# LeBot.net
KiCad netlist of a schematic drawn in Altium Designer
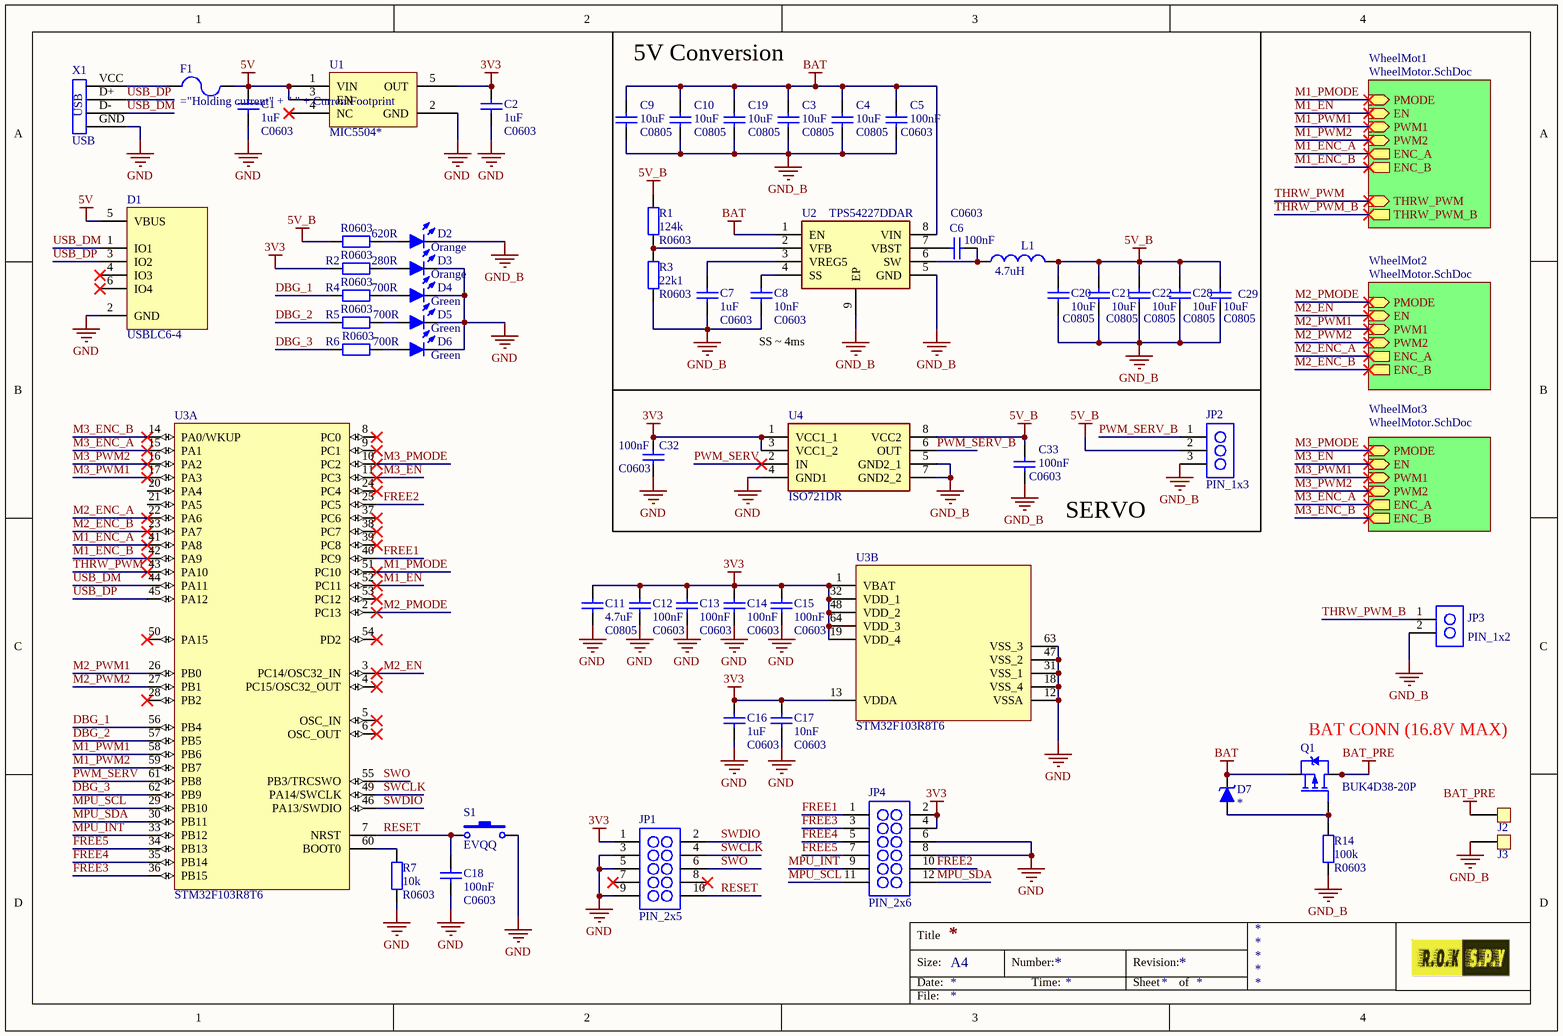
[diagram p0: LeBot.SchDoc]

(export (version "E")
  (design (tool "Eeschema 10.0.6"))
  (components
    (comp (ref "C1")
      (value "1uF*V")
      (footprint "C0603")
      (description "Ceramic capacitor")
      (fields (field (name "CAPACITANCE") "1uF"))
      (libsource (lib "SCH Passives") (part "Capacitor"))
    )
    (comp (ref "C2")
      (value "1uF*V")
      (footprint "C0603")
      (description "Ceramic capacitor")
      (fields (field (name "CAPACITANCE") "1uF"))
      (libsource (lib "SCH Passives") (part "Capacitor"))
    )
    (comp (ref "C3")
      (value "10uF*V")
      (footprint "C0805")
      (description "Ceramic capacitor")
      (fields (field (name "CAPACITANCE") "10uF"))
      (libsource (lib "SCH Passives") (part "Capacitor"))
    )
    (comp (ref "C4")
      (value "10uF*V")
      (footprint "C0805")
      (description "Ceramic capacitor")
      (fields (field (name "CAPACITANCE") "10uF"))
      (libsource (lib "SCH Passives") (part "Capacitor"))
    )
    (comp (ref "C5")
      (value "100nF*V")
      (footprint "C0603")
      (description "Ceramic capacitor")
      (fields (field (name "CAPACITANCE") "100nF"))
      (libsource (lib "SCH Passives") (part "Capacitor"))
    )
    (comp (ref "C6")
      (value "100nF*V")
      (footprint "C0603")
      (description "Ceramic capacitor")
      (fields (field (name "CAPACITANCE") "100nF"))
      (libsource (lib "SCH Passives") (part "Capacitor"))
    )
    (comp (ref "C7")
      (value "1uF*V")
      (footprint "C0603")
      (description "Ceramic capacitor")
      (fields (field (name "CAPACITANCE") "1uF"))
      (libsource (lib "SCH Passives") (part "Capacitor"))
    )
    (comp (ref "C8")
      (value "10nF*V")
      (footprint "C0603")
      (description "Ceramic capacitor")
      (fields (field (name "CAPACITANCE") "10nF"))
      (libsource (lib "SCH Passives") (part "Capacitor"))
    )
    (comp (ref "C9")
      (value "10uF*V")
      (footprint "C0805")
      (description "Ceramic capacitor")
      (fields (field (name "CAPACITANCE") "10uF"))
      (libsource (lib "SCH Passives") (part "Capacitor"))
    )
    (comp (ref "C10")
      (value "10uF*V")
      (footprint "C0805")
      (description "Ceramic capacitor")
      (fields (field (name "CAPACITANCE") "10uF"))
      (libsource (lib "SCH Passives") (part "Capacitor"))
    )
    (comp (ref "C11")
      (value "4.7uF*V")
      (footprint "C0805")
      (description "Ceramic capacitor")
      (fields (field (name "CAPACITANCE") "4.7uF"))
      (libsource (lib "SCH Passives") (part "Capacitor"))
    )
    (comp (ref "C12")
      (value "100nF*V")
      (footprint "C0603")
      (description "Ceramic capacitor")
      (fields (field (name "CAPACITANCE") "100nF"))
      (libsource (lib "SCH Passives") (part "Capacitor"))
    )
    (comp (ref "C13")
      (value "100nF*V")
      (footprint "C0603")
      (description "Ceramic capacitor")
      (fields (field (name "CAPACITANCE") "100nF"))
      (libsource (lib "SCH Passives") (part "Capacitor"))
    )
    (comp (ref "C14")
      (value "100nF*V")
      (footprint "C0603")
      (description "Ceramic capacitor")
      (fields (field (name "CAPACITANCE") "100nF"))
      (libsource (lib "SCH Passives") (part "Capacitor"))
    )
    (comp (ref "C15")
      (value "100nF*V")
      (footprint "C0603")
      (description "Ceramic capacitor")
      (fields (field (name "CAPACITANCE") "100nF"))
      (libsource (lib "SCH Passives") (part "Capacitor"))
    )
    (comp (ref "C16")
      (value "1uF*V")
      (footprint "C0603")
      (description "Ceramic capacitor")
      (fields (field (name "CAPACITANCE") "1uF"))
      (libsource (lib "SCH Passives") (part "Capacitor"))
    )
    (comp (ref "C17")
      (value "10nF*V")
      (footprint "C0603")
      (description "Ceramic capacitor")
      (fields (field (name "CAPACITANCE") "10nF"))
      (libsource (lib "SCH Passives") (part "Capacitor"))
    )
    (comp (ref "C18")
      (value "100nF*V")
      (footprint "C0603")
      (description "Ceramic capacitor")
      (fields (field (name "CAPACITANCE") "100nF"))
      (libsource (lib "SCH Passives") (part "Capacitor"))
    )
    (comp (ref "C19")
      (value "10uF*V")
      (footprint "C0805")
      (description "Ceramic capacitor")
      (fields (field (name "CAPACITANCE") "10uF"))
      (libsource (lib "SCH Passives") (part "Capacitor"))
    )
    (comp (ref "C20")
      (value "10uF*V")
      (footprint "C0805")
      (description "Ceramic capacitor")
      (fields (field (name "CAPACITANCE") "10uF"))
      (libsource (lib "SCH Passives") (part "Capacitor"))
    )
    (comp (ref "C21")
      (value "10uF*V")
      (footprint "C0805")
      (description "Ceramic capacitor")
      (fields (field (name "CAPACITANCE") "10uF"))
      (libsource (lib "SCH Passives") (part "Capacitor"))
    )
    (comp (ref "C22")
      (value "10uF*V")
      (footprint "C0805")
      (description "Ceramic capacitor")
      (fields (field (name "CAPACITANCE") "10uF"))
      (libsource (lib "SCH Passives") (part "Capacitor"))
    )
    (comp (ref "C28")
      (value "10uF*V")
      (footprint "C0805")
      (description "Ceramic capacitor")
      (fields (field (name "CAPACITANCE") "10uF"))
      (libsource (lib "SCH Passives") (part "Capacitor"))
    )
    (comp (ref "C29")
      (value "10uF*V")
      (footprint "C0805")
      (description "Ceramic capacitor")
      (fields (field (name "CAPACITANCE") "10uF"))
      (libsource (lib "SCH Passives") (part "Capacitor"))
    )
    (comp (ref "C32")
      (value "100nF*V")
      (footprint "C0603")
      (description "Ceramic capacitor")
      (fields (field (name "CAPACITANCE") "100nF"))
      (libsource (lib "SCH Passives") (part "Capacitor"))
    )
    (comp (ref "C33")
      (value "100nF*V")
      (footprint "C0603")
      (description "Ceramic capacitor")
      (fields (field (name "CAPACITANCE") "100nF"))
      (libsource (lib "SCH Passives") (part "Capacitor"))
    )
    (comp (ref "D1")
      (value "USBLC6-4")
      (footprint "SOT-236")
      (description "USB ESD Protection")
      (fields (field (name "MANUFACTURER") "ST Microelectronics"))
      (libsource (lib "SCH Diodes") (part "USBLC6-4"))
    )
    (comp (ref "D2")
      (value "~")
      (footprint "Diodes:LED_0805")
      (description "Light Emitting Diode")
      (fields (field (name "PART NUMBER") "MC011368") (field (name "COLOUR") "Orange"))
      (libsource (lib "Diodes") (part "LED"))
    )
    (comp (ref "D3")
      (value "~")
      (footprint "Diodes:LED_0805")
      (description "Light Emitting Diode")
      (fields (field (name "PART NUMBER") "MC011368") (field (name "COLOUR") "Orange"))
      (libsource (lib "Diodes") (part "LED"))
    )
    (comp (ref "D4")
      (value "~")
      (footprint "Diodes:LED_0805")
      (description "Light Emitting Diode")
      (fields (field (name "PART NUMBER") "KP-2012LSGC") (field (name "COLOUR") "Green"))
      (libsource (lib "Diodes") (part "LED"))
    )
    (comp (ref "D5")
      (value "~")
      (footprint "Diodes:LED_0805")
      (description "Light Emitting Diode")
      (fields (field (name "PART NUMBER") "KP-2012LSGC") (field (name "COLOUR") "Green"))
      (libsource (lib "Diodes") (part "LED"))
    )
    (comp (ref "D6")
      (value "~")
      (footprint "Diodes:LED_0805")
      (description "Light Emitting Diode")
      (fields (field (name "PART NUMBER") "KP-2012LSGC") (field (name "COLOUR") "Green"))
      (libsource (lib "Diodes") (part "LED"))
    )
    (comp (ref "D7")
      (value "*")
      (footprint "Diodes:SOT23-Zener")
      (libsource (lib "Diodes") (part "Zener Diode"))
    )
    (comp (ref "F1")
      (value "*A")
      (footprint "F1210")
      (description "Fuse")
      (fields (field (name "NOTE") "*A"))
      (libsource (lib "SCH Passives") (part "Fuse"))
    )
    (comp (ref "J2")
      (value "Connection_pad")
      (footprint "Connectors:Wire_Pad")
      (libsource (lib "Connectors") (part "Connection_pad"))
    )
    (comp (ref "J3")
      (value "Connection_pad")
      (footprint "Connectors:Wire_Pad")
      (libsource (lib "Connectors") (part "Connection_pad"))
    )
    (comp (ref "JP1")
      (value "PIN_2x5")
      (footprint "1.27_2X5H")
      (fields (field (name "DRAWN BY") "Erik Ilbis"))
      (libsource (lib "SCH Pinhead") (part "PIN_2x5"))
    )
    (comp (ref "JP2")
      (value "PIN_1x3")
      (footprint "1.27_1X3H")
      (fields (field (name "DRAWN BY") "Erik Ilbis"))
      (libsource (lib "SCH Pinhead") (part "PIN_1x3"))
    )
    (comp (ref "JP3")
      (value "PIN_1x2")
      (footprint "1.27_1X2H")
      (fields (field (name "DRAWN BY") "Erik Ilbis"))
      (libsource (lib "SCH Pinhead") (part "PIN_1x2"))
    )
    (comp (ref "JP4")
      (value "PIN_2x6")
      (footprint "1.27_2X6H")
      (fields (field (name "DRAWN BY") "Erik Ilbis"))
      (libsource (lib "SCH Pinhead") (part "PIN_2x6"))
    )
    (comp (ref "L1")
      (value "Inductor")
      (footprint "L73")
      (fields (field (name "INDUCTANCE") "4.7uH"))
      (libsource (lib "SCH Passives") (part "Inductor"))
    )
    (comp (ref "Q1")
      (value "BUK4D38-20P")
      (footprint "PMPB12EPX")
      (description "P-Channel MOSFET")
      (libsource (lib "Transistors") (part "P-Channel MOSFET"))
    )
    (comp (ref "R1")
      (value "124k")
      (footprint "R0603")
      (description "Resistor")
      (fields (field (name "RESISTANCE") "124k"))
      (libsource (lib "SCH Passives") (part "Resistor"))
    )
    (comp (ref "R2")
      (value "280R")
      (footprint "R0603")
      (description "Resistor")
      (fields (field (name "RESISTANCE") "280R"))
      (libsource (lib "") (part "Resistor_1"))
    )
    (comp (ref "R3")
      (value "22k1")
      (footprint "R0603")
      (description "Resistor")
      (fields (field (name "RESISTANCE") "22k1"))
      (libsource (lib "SCH Passives") (part "Resistor"))
    )
    (comp (ref "R4")
      (value "700R")
      (footprint "R0603")
      (description "Resistor")
      (fields (field (name "RESISTANCE") "700R"))
      (libsource (lib "") (part "Resistor_1"))
    )
    (comp (ref "R5")
      (value "700R")
      (footprint "R0603")
      (description "Resistor")
      (fields (field (name "RESISTANCE") "700R"))
      (libsource (lib "") (part "Resistor_1"))
    )
    (comp (ref "R6")
      (value "700R")
      (footprint "R0603")
      (description "Resistor")
      (fields (field (name "RESISTANCE") "700R"))
      (libsource (lib "") (part "Resistor_1"))
    )
    (comp (ref "R7")
      (value "10k")
      (footprint "R0603")
      (description "Resistor")
      (fields (field (name "RESISTANCE") "10k"))
      (libsource (lib "SCH Passives") (part "Resistor"))
    )
    (comp (ref "R8")
      (value "620R")
      (footprint "R0603")
      (description "Resistor")
      (fields (field (name "RESISTANCE") "620R"))
      (libsource (lib "") (part "Resistor_1"))
    )
    (comp (ref "R14")
      (value "100k")
      (footprint "R0603")
      (description "Resistor")
      (fields (field (name "RESISTANCE") "100k"))
      (libsource (lib "") (part "Resistor_2"))
    )
    (comp (ref "S1")
      (value "EVQQ")
      (footprint "EVQQ")
      (description "Switch")
      (fields
        (field (name "MANUFACTURER") "Panasonic")
        (field (name "PART NUMBER") "EVQQ")
        (field (name "DRAWN BY") "Erik Ilbis")
      )
      (libsource (lib "SCH Switch") (part "EVQQ"))
    )
    (comp (ref "U1")
      (value "MIC5504*")
      (footprint "SOT-235")
      (description "Low-dropout voltage regulator")
      (fields
        (field (name "MANUFACTURER") "Microchip/Micrel")
        (field (name "PART NUMBER") "MIC5504")
        (field (name "DRAWN BY") "Roberts Oskars Komarovskis")
      )
      (libsource (lib "SCH Voltage regulators") (part "MIC5504"))
    )
    (comp (ref "U2")
      (value "TPS54227DDAR")
      (footprint "Voltage Regulators:SOIC127P600X175-8N")
      (description "4.5-V to 18-V Input, 2-A SynchronousStep-DownConverter")
      (libsource (lib "Voltage Regulators") (part "TPS54227DDAR"))
    )
    (comp (ref "U3")
      (value "STM32F103R8T6")
      (footprint "MCU:QFP50P1200X1200X160-64N")
      (fields (field (name "DRAWN BY") "Roberts Oskars Komarovskis"))
      (libsource (lib "MCU") (part "STM32F103R8T6"))
    )
    (comp (ref "U4")
      (value "ISO721DR")
      (footprint "Voltage Regulators:SOIC127P600X175-8N")
      (description "SO72xSingleChannelHigh-SpeedDigitalIsolators")
      (libsource (lib "Misc") (part "ISO721DR"))
    )
    (comp (ref "X1")
      (value "USB")
      (footprint "USB MicroB Type 2.0")
      (libsource (lib "SCH Connectors") (part "USB"))
    )
  )
  (nets
    (net (code "1") (name "/DBG_1") (class "Default")
      (node (ref "R4") (pin "2") (pinfunction "2_2") (pintype "passive"))
      (node (ref "U3") (pin "56") (pinfunction "PB4_56") (pintype "bidirectional"))
    )
    (net (code "2") (name "/DBG_2") (class "Default")
      (node (ref "R5") (pin "2") (pinfunction "2_2") (pintype "passive"))
      (node (ref "U3") (pin "57") (pinfunction "PB5_57") (pintype "bidirectional"))
    )
    (net (code "3") (name "/DBG_3") (class "Default")
      (node (ref "R6") (pin "2") (pinfunction "2_2") (pintype "passive"))
      (node (ref "U3") (pin "62") (pinfunction "PB9_62") (pintype "bidirectional"))
    )
    (net (code "4") (name "/FREE1") (class "Default")
      (node (ref "JP4") (pin "1") (pinfunction "1_1") (pintype "passive"))
      (node (ref "U3") (pin "40") (pinfunction "PC9_40") (pintype "bidirectional"))
    )
    (net (code "5") (name "/FREE2") (class "Default")
      (node (ref "JP4") (pin "10") (pinfunction "10_10") (pintype "passive"))
      (node (ref "U3") (pin "25") (pinfunction "PC5_25") (pintype "bidirectional"))
    )
    (net (code "6") (name "/FREE3") (class "Default")
      (node (ref "JP4") (pin "3") (pinfunction "3_3") (pintype "passive"))
      (node (ref "U3") (pin "36") (pinfunction "PB15_36") (pintype "bidirectional"))
    )
    (net (code "7") (name "/FREE4") (class "Default")
      (node (ref "JP4") (pin "5") (pinfunction "5_5") (pintype "passive"))
      (node (ref "U3") (pin "35") (pinfunction "PB14_35") (pintype "bidirectional"))
    )
    (net (code "8") (name "/FREE5") (class "Default")
      (node (ref "JP4") (pin "7") (pinfunction "7_7") (pintype "passive"))
      (node (ref "U3") (pin "34") (pinfunction "PB13_34") (pintype "bidirectional"))
    )
    (net (code "9") (name "/M1_EN") (class "Default")
      (node (ref "U3") (pin "52") (pinfunction "PC11_52") (pintype "bidirectional+no_connect"))
    )
    (net (code "10") (name "/M1_ENC_A") (class "Default")
      (node (ref "U3") (pin "41") (pinfunction "PA8_41") (pintype "bidirectional+no_connect"))
    )
    (net (code "11") (name "/M1_ENC_B") (class "Default")
      (node (ref "U3") (pin "42") (pinfunction "PA9_42") (pintype "bidirectional+no_connect"))
    )
    (net (code "12") (name "/M1_PMODE") (class "Default")
      (node (ref "U3") (pin "51") (pinfunction "PC10_51") (pintype "bidirectional+no_connect"))
    )
    (net (code "13") (name "/M1_PWM1") (class "Default")
      (node (ref "U3") (pin "58") (pinfunction "PB6_58") (pintype "bidirectional"))
    )
    (net (code "14") (name "/M1_PWM2") (class "Default")
      (node (ref "U3") (pin "59") (pinfunction "PB7_59") (pintype "bidirectional"))
    )
    (net (code "15") (name "/M2_EN") (class "Default")
      (node (ref "U3") (pin "3") (pinfunction "PC14/OSC32_IN_3") (pintype "bidirectional+no_connect"))
    )
    (net (code "16") (name "/M2_ENC_A") (class "Default")
      (node (ref "U3") (pin "22") (pinfunction "PA6_22") (pintype "bidirectional+no_connect"))
    )
    (net (code "17") (name "/M2_ENC_B") (class "Default")
      (node (ref "U3") (pin "23") (pinfunction "PA7_23") (pintype "bidirectional+no_connect"))
    )
    (net (code "18") (name "/M2_PMODE") (class "Default")
      (node (ref "U3") (pin "2") (pinfunction "PC13_2") (pintype "bidirectional+no_connect"))
    )
    (net (code "19") (name "/M2_PWM1") (class "Default")
      (node (ref "U3") (pin "26") (pinfunction "PB0_26") (pintype "bidirectional"))
    )
    (net (code "20") (name "/M2_PWM2") (class "Default")
      (node (ref "U3") (pin "27") (pinfunction "PB1_27") (pintype "bidirectional"))
    )
    (net (code "21") (name "/M3_EN") (class "Default")
      (node (ref "U3") (pin "11") (pinfunction "PC3_11") (pintype "bidirectional+no_connect"))
    )
    (net (code "22") (name "/M3_ENC_A") (class "Default")
      (node (ref "U3") (pin "15") (pinfunction "PA1_15") (pintype "bidirectional+no_connect"))
    )
    (net (code "23") (name "/M3_ENC_B") (class "Default")
      (node (ref "U3") (pin "14") (pinfunction "PA0/WKUP_14") (pintype "bidirectional+no_connect"))
    )
    (net (code "24") (name "/M3_PMODE") (class "Default")
      (node (ref "U3") (pin "10") (pinfunction "PC2_10") (pintype "bidirectional+no_connect"))
    )
    (net (code "25") (name "/M3_PWM1") (class "Default")
      (node (ref "U3") (pin "17") (pinfunction "PA3_17") (pintype "bidirectional+no_connect"))
    )
    (net (code "26") (name "/M3_PWM2") (class "Default")
      (node (ref "U3") (pin "16") (pinfunction "PA2_16") (pintype "bidirectional+no_connect"))
    )
    (net (code "27") (name "/MPU_INT") (class "Default")
      (node (ref "JP4") (pin "9") (pinfunction "9_9") (pintype "passive"))
      (node (ref "U3") (pin "33") (pinfunction "PB12_33") (pintype "bidirectional"))
    )
    (net (code "28") (name "/MPU_SCL") (class "Default")
      (node (ref "JP4") (pin "11") (pinfunction "11_11") (pintype "passive"))
      (node (ref "U3") (pin "29") (pinfunction "PB10_29") (pintype "bidirectional"))
    )
    (net (code "29") (name "/MPU_SDA") (class "Default")
      (node (ref "JP4") (pin "12") (pinfunction "12_12") (pintype "passive"))
      (node (ref "U3") (pin "30") (pinfunction "PB11_30") (pintype "bidirectional"))
    )
    (net (code "30") (name "/PWM_SERV") (class "Default")
      (node (ref "U3") (pin "61") (pinfunction "PB8_61") (pintype "bidirectional"))
      (node (ref "U4") (pin "2") (pinfunction "IN_2") (pintype "passive"))
    )
    (net (code "31") (name "/PWM_SERV_B") (class "Default")
      (node (ref "JP2") (pin "1") (pinfunction "1_1") (pintype "passive"))
      (node (ref "U4") (pin "6") (pinfunction "OUT_6") (pintype "passive"))
    )
    (net (code "32") (name "/RESET") (class "Default")
      (node (ref "C18") (pin "2") (pinfunction "2_2") (pintype "passive"))
      (node (ref "JP1") (pin "10") (pinfunction "10_10") (pintype "passive"))
      (node (ref "S1") (pin "1") (pinfunction "1_1") (pintype "passive"))
      (node (ref "U3") (pin "7") (pinfunction "NRST_7") (pintype "passive"))
    )
    (net (code "33") (name "/SWCLK") (class "Default")
      (node (ref "JP1") (pin "4") (pinfunction "4_4") (pintype "passive"))
      (node (ref "U3") (pin "49") (pinfunction "PA14/SWCLK_49") (pintype "bidirectional"))
    )
    (net (code "34") (name "/SWDIO") (class "Default")
      (node (ref "JP1") (pin "2") (pinfunction "2_2") (pintype "passive"))
      (node (ref "U3") (pin "46") (pinfunction "PA13/SWDIO_46") (pintype "bidirectional"))
    )
    (net (code "35") (name "/SWO") (class "Default")
      (node (ref "JP1") (pin "6") (pinfunction "6_6") (pintype "passive"))
      (node (ref "U3") (pin "55") (pinfunction "PB3/TRCSWO_55") (pintype "bidirectional"))
    )
    (net (code "36") (name "/THRW_PWM") (class "Default")
      (node (ref "U3") (pin "43") (pinfunction "PA10_43") (pintype "bidirectional+no_connect"))
    )
    (net (code "37") (name "/THRW_PWM_B") (class "Default")
      (node (ref "JP3") (pin "1") (pinfunction "1_1") (pintype "passive"))
    )
    (net (code "38") (name "/USB_DM") (class "Default")
      (node (ref "D1") (pin "1") (pinfunction "IO1_1") (pintype "passive"))
      (node (ref "U3") (pin "44") (pinfunction "PA11_44") (pintype "bidirectional"))
      (node (ref "X1") (pin "D-") (pintype "passive"))
    )
    (net (code "39") (name "/USB_DP") (class "Default")
      (node (ref "D1") (pin "3") (pinfunction "IO2_3") (pintype "passive"))
      (node (ref "U3") (pin "45") (pinfunction "PA12_45") (pintype "bidirectional"))
      (node (ref "X1") (pin "D+") (pintype "passive"))
    )
    (net (code "40") (name "3V3") (class "Default")
      (node (ref "C11") (pin "2") (pinfunction "2_2") (pintype "passive"))
      (node (ref "C12") (pin "2") (pinfunction "2_2") (pintype "passive"))
      (node (ref "C13") (pin "2") (pinfunction "2_2") (pintype "passive"))
      (node (ref "C14") (pin "2") (pinfunction "2_2") (pintype "passive"))
      (node (ref "C15") (pin "2") (pinfunction "2_2") (pintype "passive"))
      (node (ref "C16") (pin "2") (pinfunction "2_2") (pintype "passive"))
      (node (ref "C17") (pin "2") (pinfunction "2_2") (pintype "passive"))
      (node (ref "C2") (pin "2") (pinfunction "2_2") (pintype "passive"))
      (node (ref "C32") (pin "2") (pinfunction "2_2") (pintype "passive"))
      (node (ref "JP1") (pin "1") (pinfunction "1_1") (pintype "passive"))
      (node (ref "JP4") (pin "2") (pinfunction "2_2") (pintype "passive"))
      (node (ref "JP4") (pin "4") (pinfunction "4_4") (pintype "passive"))
      (node (ref "R2") (pin "2") (pinfunction "2_2") (pintype "passive"))
      (node (ref "U1") (pin "5") (pinfunction "OUT_5") (pintype "passive"))
      (node (ref "U3") (pin "1") (pinfunction "VBAT_1") (pintype "passive"))
      (node (ref "U3") (pin "13") (pinfunction "VDDA_13") (pintype "passive"))
      (node (ref "U3") (pin "19") (pinfunction "VDD_4_19") (pintype "passive"))
      (node (ref "U3") (pin "32") (pinfunction "VDD_1_32") (pintype "passive"))
      (node (ref "U3") (pin "48") (pinfunction "VDD_2_48") (pintype "passive"))
      (node (ref "U3") (pin "64") (pinfunction "VDD_3_64") (pintype "passive"))
      (node (ref "U4") (pin "1") (pinfunction "VCC1_1_1") (pintype "passive"))
      (node (ref "U4") (pin "3") (pinfunction "VCC1_2_3") (pintype "passive"))
    )
    (net (code "41") (name "5V") (class "Default")
      (node (ref "C1") (pin "2") (pinfunction "2_2") (pintype "passive"))
      (node (ref "D1") (pin "5") (pinfunction "VBUS_5") (pintype "passive"))
      (node (ref "F1") (pin "2") (pinfunction "2_2") (pintype "passive"))
      (node (ref "U1") (pin "1") (pinfunction "VIN_1") (pintype "passive"))
      (node (ref "U1") (pin "3") (pinfunction "EN_3") (pintype "passive"))
    )
    (net (code "42") (name "5V_B") (class "Default")
      (node (ref "C20") (pin "2") (pinfunction "2_2") (pintype "passive"))
      (node (ref "C21") (pin "2") (pinfunction "2_2") (pintype "passive"))
      (node (ref "C22") (pin "2") (pinfunction "2_2") (pintype "passive"))
      (node (ref "C28") (pin "2") (pinfunction "2_2") (pintype "passive"))
      (node (ref "C29") (pin "2") (pinfunction "2_2") (pintype "passive"))
      (node (ref "C33") (pin "2") (pinfunction "2_2") (pintype "passive"))
      (node (ref "JP2") (pin "2") (pinfunction "2_2") (pintype "passive"))
      (node (ref "L1") (pin "2") (pinfunction "2_2") (pintype "passive"))
      (node (ref "R1") (pin "2") (pinfunction "2_2") (pintype "passive"))
      (node (ref "R8") (pin "2") (pinfunction "2_2") (pintype "passive"))
      (node (ref "U4") (pin "8") (pinfunction "VCC2_8") (pintype "passive"))
    )
    (net (code "43") (name "BAT") (class "Default")
      (node (ref "C10") (pin "2") (pinfunction "2_2") (pintype "passive"))
      (node (ref "C19") (pin "2") (pinfunction "2_2") (pintype "passive"))
      (node (ref "C3") (pin "2") (pinfunction "2_2") (pintype "passive"))
      (node (ref "C4") (pin "2") (pinfunction "2_2") (pintype "passive"))
      (node (ref "C5") (pin "2") (pinfunction "2_2") (pintype "passive"))
      (node (ref "C9") (pin "2") (pinfunction "2_2") (pintype "passive"))
      (node (ref "D7") (pin "2") (pinfunction "K_2") (pintype "passive"))
      (node (ref "Q1") (pin "1") (pinfunction "S_1") (pintype "passive"))
      (node (ref "U2") (pin "1") (pinfunction "EN_1") (pintype "passive"))
      (node (ref "U2") (pin "8") (pinfunction "VIN_8") (pintype "passive"))
    )
    (net (code "44") (name "BAT_PRE") (class "Default")
      (node (ref "J2") (pin "1") (pinfunction "*_1") (pintype "passive"))
      (node (ref "Q1") (pin "3") (pinfunction "D_3") (pintype "passive"))
      (node (ref "Q1") (pin "D0") (pinfunction "D_D0") (pintype "passive"))
      (node (ref "Q1") (pin "D1") (pinfunction "D_D1") (pintype "passive"))
      (node (ref "Q1") (pin "D2") (pinfunction "D_D2") (pintype "passive"))
    )
    (net (code "45") (name "GND") (class "Default")
      (node (ref "C1") (pin "1") (pinfunction "1_1") (pintype "passive"))
      (node (ref "C11") (pin "1") (pinfunction "1_1") (pintype "passive"))
      (node (ref "C12") (pin "1") (pinfunction "1_1") (pintype "passive"))
      (node (ref "C13") (pin "1") (pinfunction "1_1") (pintype "passive"))
      (node (ref "C14") (pin "1") (pinfunction "1_1") (pintype "passive"))
      (node (ref "C15") (pin "1") (pinfunction "1_1") (pintype "passive"))
      (node (ref "C16") (pin "1") (pinfunction "1_1") (pintype "passive"))
      (node (ref "C17") (pin "1") (pinfunction "1_1") (pintype "passive"))
      (node (ref "C18") (pin "1") (pinfunction "1_1") (pintype "passive"))
      (node (ref "C2") (pin "1") (pinfunction "1_1") (pintype "passive"))
      (node (ref "C32") (pin "1") (pinfunction "1_1") (pintype "passive"))
      (node (ref "D1") (pin "2") (pinfunction "GND_2") (pintype "passive"))
      (node (ref "D3") (pin "2") (pinfunction "K_2") (pintype "passive"))
      (node (ref "D4") (pin "2") (pinfunction "K_2") (pintype "passive"))
      (node (ref "D5") (pin "2") (pinfunction "K_2") (pintype "passive"))
      (node (ref "D6") (pin "2") (pinfunction "K_2") (pintype "passive"))
      (node (ref "JP1") (pin "3") (pinfunction "3_3") (pintype "passive"))
      (node (ref "JP1") (pin "5") (pinfunction "5_5") (pintype "passive"))
      (node (ref "JP1") (pin "9") (pinfunction "9_9") (pintype "passive"))
      (node (ref "JP4") (pin "6") (pinfunction "6_6") (pintype "passive"))
      (node (ref "JP4") (pin "8") (pinfunction "8_8") (pintype "passive"))
      (node (ref "R7") (pin "1") (pinfunction "1_1") (pintype "passive"))
      (node (ref "S1") (pin "2") (pinfunction "2_2") (pintype "passive"))
      (node (ref "U1") (pin "2") (pinfunction "GND_2") (pintype "passive"))
      (node (ref "U3") (pin "12") (pinfunction "VSSA_12") (pintype "passive"))
      (node (ref "U3") (pin "18") (pinfunction "VSS_4_18") (pintype "passive"))
      (node (ref "U3") (pin "31") (pinfunction "VSS_1_31") (pintype "passive"))
      (node (ref "U3") (pin "47") (pinfunction "VSS_2_47") (pintype "passive"))
      (node (ref "U3") (pin "63") (pinfunction "VSS_3_63") (pintype "passive"))
      (node (ref "U4") (pin "4") (pinfunction "GND1_4") (pintype "passive"))
      (node (ref "X1") (pin "GND") (pintype "passive"))
    )
    (net (code "46") (name "GND_B") (class "Default")
      (node (ref "C10") (pin "1") (pinfunction "1_1") (pintype "passive"))
      (node (ref "C19") (pin "1") (pinfunction "1_1") (pintype "passive"))
      (node (ref "C20") (pin "1") (pinfunction "1_1") (pintype "passive"))
      (node (ref "C21") (pin "1") (pinfunction "1_1") (pintype "passive"))
      (node (ref "C22") (pin "1") (pinfunction "1_1") (pintype "passive"))
      (node (ref "C28") (pin "1") (pinfunction "1_1") (pintype "passive"))
      (node (ref "C29") (pin "1") (pinfunction "1_1") (pintype "passive"))
      (node (ref "C3") (pin "1") (pinfunction "1_1") (pintype "passive"))
      (node (ref "C33") (pin "1") (pinfunction "1_1") (pintype "passive"))
      (node (ref "C4") (pin "1") (pinfunction "1_1") (pintype "passive"))
      (node (ref "C5") (pin "1") (pinfunction "1_1") (pintype "passive"))
      (node (ref "C7") (pin "1") (pinfunction "1_1") (pintype "passive"))
      (node (ref "C8") (pin "1") (pinfunction "1_1") (pintype "passive"))
      (node (ref "C9") (pin "1") (pinfunction "1_1") (pintype "passive"))
      (node (ref "D2") (pin "2") (pinfunction "K_2") (pintype "passive"))
      (node (ref "J3") (pin "1") (pinfunction "*_1") (pintype "passive"))
      (node (ref "JP2") (pin "3") (pinfunction "3_3") (pintype "passive"))
      (node (ref "JP3") (pin "2") (pinfunction "2_2") (pintype "passive"))
      (node (ref "R14") (pin "2") (pinfunction "2_2") (pintype "passive"))
      (node (ref "R3") (pin "1") (pinfunction "1_1") (pintype "passive"))
      (node (ref "U2") (pin "5") (pinfunction "GND_5") (pintype "passive"))
      (node (ref "U2") (pin "9") (pinfunction "EP_9") (pintype "passive"))
      (node (ref "U4") (pin "5") (pinfunction "GND2_1_5") (pintype "passive"))
      (node (ref "U4") (pin "7") (pinfunction "GND2_2_7") (pintype "passive"))
    )
    (net (code "47") (name "Net-(D2-A)") (class "Default")
      (node (ref "D2") (pin "1") (pinfunction "A_1") (pintype "passive"))
      (node (ref "R8") (pin "1") (pinfunction "1_1") (pintype "passive"))
    )
    (net (code "48") (name "Net-(D3-A)") (class "Default")
      (node (ref "D3") (pin "1") (pinfunction "A_1") (pintype "passive"))
      (node (ref "R2") (pin "1") (pinfunction "1_1") (pintype "passive"))
    )
    (net (code "49") (name "Net-(D4-A)") (class "Default")
      (node (ref "D4") (pin "1") (pinfunction "A_1") (pintype "passive"))
      (node (ref "R4") (pin "1") (pinfunction "1_1") (pintype "passive"))
    )
    (net (code "50") (name "Net-(D5-A)") (class "Default")
      (node (ref "D5") (pin "1") (pinfunction "A_1") (pintype "passive"))
      (node (ref "R5") (pin "1") (pinfunction "1_1") (pintype "passive"))
    )
    (net (code "51") (name "Net-(D6-A)") (class "Default")
      (node (ref "D6") (pin "1") (pinfunction "A_1") (pintype "passive"))
      (node (ref "R6") (pin "1") (pinfunction "1_1") (pintype "passive"))
    )
    (net (code "52") (name "Net-(D7-A)") (class "Default")
      (node (ref "D7") (pin "1") (pinfunction "A_1") (pintype "passive"))
      (node (ref "Q1") (pin "2") (pinfunction "G_2") (pintype "passive"))
      (node (ref "R14") (pin "1") (pinfunction "1_1") (pintype "passive"))
    )
    (net (code "53") (name "Net-(F1-Pad1)") (class "Default")
      (node (ref "F1") (pin "1") (pinfunction "1_1") (pintype "passive"))
      (node (ref "X1") (pin "VCC") (pintype "passive"))
    )
    (net (code "54") (name "Net-(U2-SS)") (class "Default")
      (node (ref "C8") (pin "2") (pinfunction "2_2") (pintype "passive"))
      (node (ref "U2") (pin "4") (pinfunction "SS_4") (pintype "passive"))
    )
    (net (code "55") (name "Net-(U2-SW)") (class "Default")
      (node (ref "C6") (pin "1") (pinfunction "1_1") (pintype "passive"))
      (node (ref "L1") (pin "1") (pinfunction "1_1") (pintype "passive"))
      (node (ref "U2") (pin "6") (pinfunction "SW_6") (pintype "passive"))
    )
    (net (code "56") (name "Net-(U2-VBST)") (class "Default")
      (node (ref "C6") (pin "2") (pinfunction "2_2") (pintype "passive"))
      (node (ref "U2") (pin "7") (pinfunction "VBST_7") (pintype "passive"))
    )
    (net (code "57") (name "Net-(U2-VFB)") (class "Default")
      (node (ref "R1") (pin "1") (pinfunction "1_1") (pintype "passive"))
      (node (ref "R3") (pin "2") (pinfunction "2_2") (pintype "passive"))
      (node (ref "U2") (pin "2") (pinfunction "VFB_2") (pintype "passive"))
    )
    (net (code "58") (name "Net-(U2-VREG5)") (class "Default")
      (node (ref "C7") (pin "2") (pinfunction "2_2") (pintype "passive"))
      (node (ref "U2") (pin "3") (pinfunction "VREG5_3") (pintype "passive"))
    )
    (net (code "59") (name "Net-(U3A-BOOT0)") (class "Default")
      (node (ref "R7") (pin "2") (pinfunction "2_2") (pintype "passive"))
      (node (ref "U3") (pin "60") (pinfunction "BOOT0_60") (pintype "passive"))
    )
    (net (code "60") (name "unconnected-(D1-IO3-Pad4)") (class "Default")
      (node (ref "D1") (pin "4") (pinfunction "IO3_4") (pintype "passive+no_connect"))
    )
    (net (code "61") (name "unconnected-(D1-IO4-Pad6)") (class "Default")
      (node (ref "D1") (pin "6") (pinfunction "IO4_6") (pintype "passive+no_connect"))
    )
    (net (code "62") (name "unconnected-(JP1-Pad7)") (class "Default")
      (node (ref "JP1") (pin "7") (pinfunction "7_7") (pintype "passive+no_connect"))
    )
    (net (code "63") (name "unconnected-(JP1-Pad8)") (class "Default")
      (node (ref "JP1") (pin "8") (pinfunction "8_8") (pintype "passive+no_connect"))
    )
    (net (code "64") (name "unconnected-(U1-NC-Pad4)") (class "Default")
      (node (ref "U1") (pin "4") (pinfunction "NC_4") (pintype "passive+no_connect"))
    )
    (net (code "65") (name "unconnected-(U3A-OSC_IN-Pad5)") (class "Default")
      (node (ref "U3") (pin "5") (pinfunction "OSC_IN_5") (pintype "bidirectional+no_connect"))
    )
    (net (code "66") (name "unconnected-(U3A-OSC_OUT-Pad6)") (class "Default")
      (node (ref "U3") (pin "6") (pinfunction "OSC_OUT_6") (pintype "bidirectional+no_connect"))
    )
    (net (code "67") (name "unconnected-(U3A-PA4-Pad20)") (class "Default")
      (node (ref "U3") (pin "20") (pinfunction "PA4_20") (pintype "bidirectional"))
    )
    (net (code "68") (name "unconnected-(U3A-PA5-Pad21)") (class "Default")
      (node (ref "U3") (pin "21") (pinfunction "PA5_21") (pintype "bidirectional"))
    )
    (net (code "69") (name "unconnected-(U3A-PA15-Pad50)") (class "Default")
      (node (ref "U3") (pin "50") (pinfunction "PA15_50") (pintype "bidirectional+no_connect"))
    )
    (net (code "70") (name "unconnected-(U3A-PB2-Pad28)") (class "Default")
      (node (ref "U3") (pin "28") (pinfunction "PB2_28") (pintype "bidirectional+no_connect"))
    )
    (net (code "71") (name "unconnected-(U3A-PC0-Pad8)") (class "Default")
      (node (ref "U3") (pin "8") (pinfunction "PC0_8") (pintype "bidirectional+no_connect"))
    )
    (net (code "72") (name "unconnected-(U3A-PC1-Pad9)") (class "Default")
      (node (ref "U3") (pin "9") (pinfunction "PC1_9") (pintype "bidirectional+no_connect"))
    )
    (net (code "73") (name "unconnected-(U3A-PC4-Pad24)") (class "Default")
      (node (ref "U3") (pin "24") (pinfunction "PC4_24") (pintype "bidirectional+no_connect"))
    )
    (net (code "74") (name "unconnected-(U3A-PC6-Pad37)") (class "Default")
      (node (ref "U3") (pin "37") (pinfunction "PC6_37") (pintype "bidirectional+no_connect"))
    )
    (net (code "75") (name "unconnected-(U3A-PC7-Pad38)") (class "Default")
      (node (ref "U3") (pin "38") (pinfunction "PC7_38") (pintype "bidirectional+no_connect"))
    )
    (net (code "76") (name "unconnected-(U3A-PC8-Pad39)") (class "Default")
      (node (ref "U3") (pin "39") (pinfunction "PC8_39") (pintype "bidirectional+no_connect"))
    )
    (net (code "77") (name "unconnected-(U3A-PC12-Pad53)") (class "Default")
      (node (ref "U3") (pin "53") (pinfunction "PC12_53") (pintype "bidirectional+no_connect"))
    )
    (net (code "78") (name "unconnected-(U3A-PC15{slash}OSC32_OUT-Pad4)") (class "Default")
      (node (ref "U3") (pin "4") (pinfunction "PC15/OSC32_OUT_4") (pintype "bidirectional+no_connect"))
    )
    (net (code "79") (name "unconnected-(U3A-PD2-Pad54)") (class "Default")
      (node (ref "U3") (pin "54") (pinfunction "PD2_54") (pintype "bidirectional+no_connect"))
    )
  )
)
